# Power.net
KiCad netlist of a schematic drawn in Altium Designer
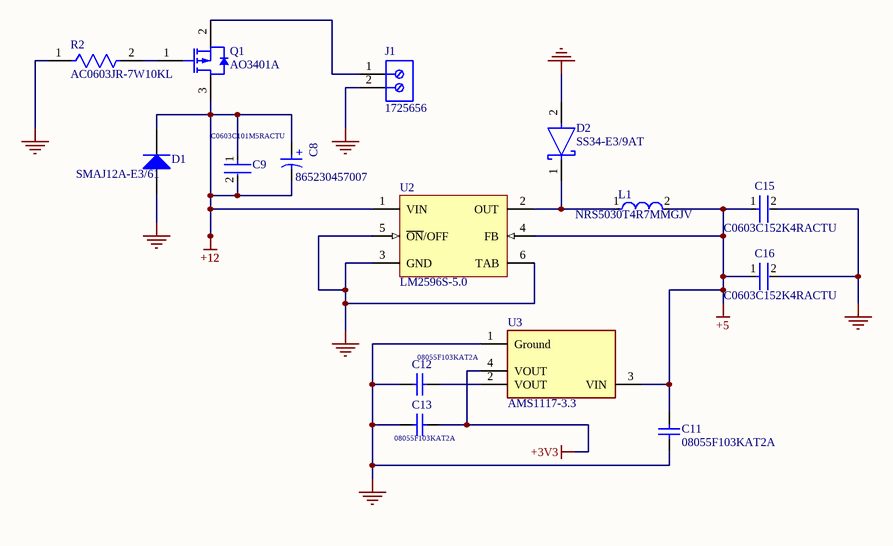
[diagram p0: Power.SchDoc]

(export (version "E")
  (design (tool "Eeschema 10.0.6"))
  (components
    (comp (ref "C8")
      (value "865230457007")
      (footprint "WCAP-AS5H_D10H10.5")
      (description "WCAP-AS5H Aluminum Electrolytic Capacitors")
      (fields (field (name "TOLERANCE") "20%"))
      (libsource (lib "Altium Content Vault") (part "Capacitor_Polarized"))
    )
    (comp (ref "C9")
      (value "C0603C101M5RACTU")
      (footprint "FP-C0603C-CF-MFG")
      (description "C0603 100 pF X7R 30ppm/°C 20.00% 50 V")
      (fields (field (name "OCTOPART") "https://octopart.com/c0603c101m5ractu-kemet-12542883"))
      (libsource (lib "Altium Content Vault") (part "b4654b650e69147ec39a6b967a45e02"))
    )
    (comp (ref "C11")
      (value "08055F103KAT2A")
      (footprint "CAPC2013X140X50LL20T25")
      (fields (field (name "MANUFACTURER") "AVX Interconnect / Elco"))
      (libsource (lib "Altium Content Vault") (part "CAP"))
    )
    (comp (ref "C12")
      (value "08055F103KAT2A")
      (footprint "CAPC2013X140X50LL20T25")
      (fields (field (name "MANUFACTURER") "AVX Interconnect / Elco"))
      (libsource (lib "Altium Content Vault") (part "CAP"))
    )
    (comp (ref "C13")
      (value "08055F103KAT2A")
      (footprint "CAPC2013X140X50LL20T25")
      (fields (field (name "MANUFACTURER") "AVX Interconnect / Elco"))
      (libsource (lib "Altium Content Vault") (part "CAP"))
    )
    (comp (ref "C15")
      (value "C0603C152K4RACTU")
      (footprint "FP-C0603C-CF-MFG")
      (description "C0603 1,500 pF X7R 30ppm/°C 10.00% 16 V")
      (fields (field (name "MANUFACTURER") "KEMET"))
      (libsource (lib "Altium Content Vault") (part "b4654b650e69147ec39a6b967a45e02"))
    )
    (comp (ref "C16")
      (value "C0603C152K4RACTU")
      (footprint "FP-C0603C-CF-MFG")
      (description "C0603 1,500 pF X7R 30ppm/°C 10.00% 16 V")
      (fields (field (name "MANUFACTURER") "KEMET"))
      (libsource (lib "Altium Content Vault") (part "b4654b650e69147ec39a6b967a45e02"))
    )
    (comp (ref "D1")
      (value "SMAJ12A-E3/61")
      (footprint "VISH-DO-214AC-2_N")
      (fields (field (name "MANUFACTURER") "Vishay Semiconductor"))
      (libsource (lib "Altium Content Vault") (part "VISH-K1A2-2"))
    )
    (comp (ref "D2")
      (value "SS34-E3/9AT")
      (footprint "FP-SMC-MFG")
      (description "DIODE SCHOTTKY 40V 3A DO214AB")
      (libsource (lib "Altium Content Vault") (part "c1678fac7984e62e0809fbf79c06691"))
    )
    (comp (ref "J1")
      (value "1725656")
      (footprint "PHOE-1725656-2")
      (description "Male Header, Pitch 2.54 mm, 1 x 2 Position, Height 9 mm, Tail Length 3.5 mm")
      (fields (field (name "MANUFACTURER") "Phoenix Contact"))
      (libsource (lib "Altium Content Vault") (part "CN-1P-F-TB2"))
    )
    (comp (ref "L1")
      (value "NRS5030T4R7MMGJV")
      (footprint "FP-NRS5030-H_3_1-MFG")
      (description "Inductor Power Shielded Wirewound 4.7uH 20% 100KHz Ferrite 2.6A 45.5mΩ DCR Automotive T/R")
      (fields (field (name "TOLERANCE") "20%"))
      (libsource (lib "Altium Content Vault") (part "725321dda6339637d4d059423bc1c3c"))
    )
    (comp (ref "Q1")
      (value "AO3401A")
      (footprint "AO-SOT-23-3L_V")
      (description "P-Channel MOSFET, 30 V, 4 A, -55 to 150 degC, 3-Pin SOT-23-3L, RoHS, Tape and Reel")
      (fields (field (name "MANUFACTURER") "Alpha and Omega"))
      (libsource (lib "Altium Content Vault") (part "PEMOS-GSD-3"))
    )
    (comp (ref "R2")
      (value "AC0603JR-7W10KL")
      (footprint "FP-AC0603-IPC_A")
      (description "RES 10kΩ 5.00% 0.2W 0603")
      (libsource (lib "Altium Content Vault") (part "1029c3af85768c4190bb7ad29bc67b5"))
    )
    (comp (ref "U2")
      (value "LM2596S-5.0")
      (footprint "KTT0005B_L")
      (description "SIMPLE SWITCHER® Power Converter 150 KHz 3A Step-Down Voltage Regulator, 5-pin TO-263")
      (fields (field (name "MANUFACTURER") "Texas Instruments"))
      (libsource (lib "Altium Content Vault") (part "PM-REG-LM2575HVS-12"))
    )
    (comp (ref "U3")
      (value "AMS1117-3.3")
      (footprint "FP-AMS1117-IPC_C")
      (description "LDO Voltage Regulators 1A, 3.3V")
      (fields
        (field (name "OCTOPART") "https://octopart.com/ams1117-3.3-advanced+monolithic+systems-25899300")
        (field (name "MANUFACTURER") "Advanced Monolithic Systems")
      )
      (libsource (lib "Altium Content Vault") (part "8bdbb5f8e77002000e30dd2845d0354"))
    )
  )
  (nets
    (net (code "1") (name "+3V3") (class "Default")
      (node (ref "C13") (pin "1") (pinfunction "1_1") (pintype "passive"))
      (node (ref "U3") (pin "4") (pinfunction "VOUT_4") (pintype "passive"))
    )
    (net (code "2") (name "+5") (class "Default")
      (node (ref "C11") (pin "2") (pinfunction "2_2") (pintype "passive"))
      (node (ref "C15") (pin "1") (pinfunction "1_1") (pintype "passive"))
      (node (ref "C16") (pin "1") (pinfunction "1_1") (pintype "passive"))
      (node (ref "L1") (pin "2") (pinfunction "2_2") (pintype "passive"))
      (node (ref "U2") (pin "4") (pinfunction "FB_4") (pintype "input"))
      (node (ref "U3") (pin "3") (pinfunction "VIN_3") (pintype "power_in"))
    )
    (net (code "3") (name "+12") (class "Default")
      (node (ref "C8") (pin "1") (pinfunction "P_1") (pintype "passive"))
      (node (ref "C8") (pin "2") (pinfunction "N_2") (pintype "passive"))
      (node (ref "C9") (pin "1") (pinfunction "1_1") (pintype "passive"))
      (node (ref "C9") (pin "2") (pinfunction "2_2") (pintype "passive"))
      (node (ref "D1") (pin "1") (pinfunction "K_1") (pintype "passive"))
      (node (ref "Q1") (pin "3") (pinfunction "DRAIN_3") (pintype "passive"))
      (node (ref "U2") (pin "1") (pinfunction "VIN_1") (pintype "power_in"))
    )
    (net (code "4") (name "<NO NET>") (class "Default")
      (node (ref "C11") (pin "1") (pinfunction "1_1") (pintype "passive"))
      (node (ref "C12") (pin "2") (pinfunction "2_2") (pintype "passive"))
      (node (ref "C13") (pin "2") (pinfunction "2_2") (pintype "passive"))
      (node (ref "C15") (pin "2") (pinfunction "2_2") (pintype "passive"))
      (node (ref "C16") (pin "2") (pinfunction "2_2") (pintype "passive"))
      (node (ref "D1") (pin "2") (pinfunction "A_2") (pintype "passive"))
      (node (ref "D2") (pin "2") (pinfunction "A_2") (pintype "passive"))
      (node (ref "J1") (pin "2") (pinfunction "2_2") (pintype "passive"))
      (node (ref "R2") (pin "1") (pinfunction "1_1") (pintype "passive"))
      (node (ref "U2") (pin "3") (pinfunction "GND_3") (pintype "power_in"))
      (node (ref "U2") (pin "5") (pinfunction "~{ON}/OFF_5") (pintype "input"))
      (node (ref "U2") (pin "6") (pinfunction "TAB_6") (pintype "power_in"))
      (node (ref "U3") (pin "1") (pinfunction "Ground_1") (pintype "power_in"))
    )
    (net (code "5") (name "Net-(C12-Pad1)") (class "Default")
      (node (ref "C12") (pin "1") (pinfunction "1_1") (pintype "passive"))
      (node (ref "U3") (pin "2") (pinfunction "VOUT_2") (pintype "passive"))
    )
    (net (code "6") (name "Net-(D2-C)") (class "Default")
      (node (ref "D2") (pin "1") (pinfunction "C_1") (pintype "passive"))
      (node (ref "L1") (pin "1") (pinfunction "1_1") (pintype "passive"))
      (node (ref "U2") (pin "2") (pinfunction "OUT_2") (pintype "power_in"))
    )
    (net (code "7") (name "Net-(Q1-GATE)") (class "Default")
      (node (ref "Q1") (pin "1") (pinfunction "GATE_1") (pintype "passive"))
      (node (ref "R2") (pin "2") (pinfunction "2_2") (pintype "passive"))
    )
    (net (code "8") (name "Net-(Q1-SOURCE)") (class "Default")
      (node (ref "J1") (pin "1") (pinfunction "1_1") (pintype "passive"))
      (node (ref "Q1") (pin "2") (pinfunction "SOURCE_2") (pintype "passive"))
    )
  )
)
